# 3.net
KiCad netlist of a schematic drawn in Altium Designer
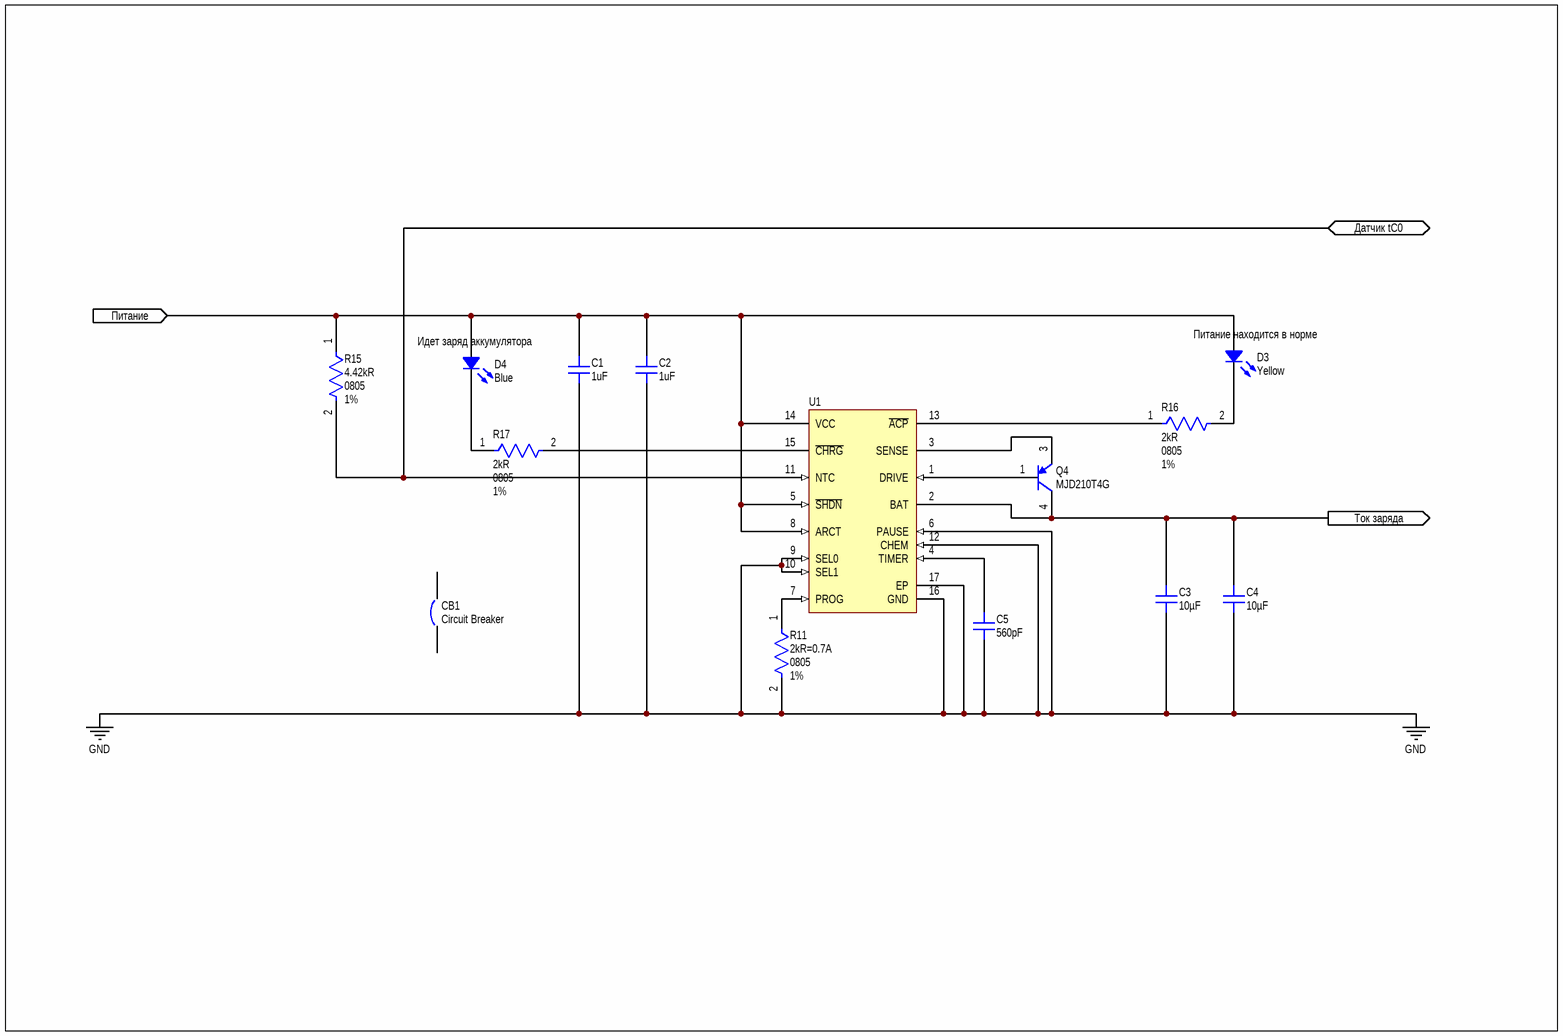
[diagram p0: Блок3.SchDoc]

(export (version "E")
  (design (tool "Eeschema 10.0.6"))
  (components
    (comp (ref "C1")
      (value "1uF")
      (footprint "CAP 1206_3216 - 1.2MM")
      (description "CAP CER 1UF 50V X7R 1206")
      (fields (field (name "PART NUMBER") "C1206C105M5RACTU") (field (name "MANUFACTURER") "KEMET"))
      (libsource (lib "Celestial Altium Library - altium_library") (part "Capacitor"))
    )
    (comp (ref "C2")
      (value "1uF")
      (footprint "CAP 1206_3216 - 1.2MM")
      (description "CAP CER 1UF 50V X7R 1206")
      (fields (field (name "PART NUMBER") "C1206C105M5RACTU") (field (name "MANUFACTURER") "KEMET"))
      (libsource (lib "Celestial Altium Library - altium_library") (part "Capacitor"))
    )
    (comp (ref "C3")
      (value "10µF")
      (footprint "CAP 1206_3216 - 1.0MM")
      (description "CAP CER 10UF 16V X5R 1206")
      (fields (field (name "PART NUMBER") "EMK316BJ106MD-T") (field (name "MANUFACTURER") "Taiyo Yuden"))
      (libsource (lib "Celestial Altium Library - altium_library") (part "Capacitor"))
    )
    (comp (ref "C4")
      (value "10µF")
      (footprint "CAP 1206_3216 - 1.0MM")
      (description "CAP CER 10UF 16V X5R 1206")
      (fields (field (name "PART NUMBER") "EMK316BJ106MD-T") (field (name "MANUFACTURER") "Taiyo Yuden"))
      (libsource (lib "Celestial Altium Library - altium_library") (part "Capacitor"))
    )
    (comp (ref "C5")
      (value "560pF")
      (footprint "CAP 1206_3216 - 0.8MM")
      (description "CAP CER 560PF 50V NPO 1206")
      (fields (field (name "PART NUMBER") "CC1206JRNPO9BN561") (field (name "MANUFACTURER") "Yageo"))
      (libsource (lib "Celestial Altium Library - altium_library") (part "Capacitor"))
    )
    (comp (ref "CB1")
      (value "Circuit Breaker")
      (footprint "SPST-2")
      (fields (field (name "PUBLISHER") "Altium Limited"))
      (libsource (lib "Miscellaneous Devices") (part "Circuit Breaker"))
    )
    (comp (ref "D3")
      (value "Yellow")
      (footprint "LED 1206_3216 YELLOW")
      (description "LED YELLOW CLEAR 2SMD")
      (fields
        (field (name "PART NUMBER") "APTD3216SYCK")
        (field (name "MANUFACTURER") "Kingbright")
        (field (name "PARAMETER 1") "Питание находится в норме")
      )
      (libsource (lib "Celestial Altium Library - altium_library") (part "LED"))
    )
    (comp (ref "D4")
      (value "Blue")
      (footprint "LED 1206_3216 BLUE")
      (description "LED BLUE CLEAR 1206 SMD")
      (fields
        (field (name "PART NUMBER") "IN-S126ATB")
        (field (name "MANUFACTURER") "Inolux")
        (field (name "PARAMETER 1") "Идет заряд аккумулятора")
      )
      (libsource (lib "Celestial Altium Library - altium_library") (part "LED"))
    )
    (comp (ref "Q4")
      (value "MJD210T4G")
      (footprint "ONSC-DPAK-3-369C-01_V")
      (description "Complementary Plastic Power Transistor, PNP Silicon, 3-Pin DPAK, Pb-Free, Tape and Reel")
      (fields (field (name "MANUFACTURER") "On Semiconductor"))
      (libsource (lib "Altium Content Vault") (part "ONSC-PNP-B1E3C4-3_A"))
    )
    (comp (ref "R11")
      (value "MC01W0805110K")
      (footprint "FP-MC01W0805-IPC_C")
      (description "Resistor, 10K, 0.1W, 1%, 0805, Reel")
      (fields
        (field (name "RESISTANCE") "2kR=0.7A")
        (field (name "CASE/PACKAGE") "0805")
        (field (name "TOLERANCE") "1%")
        (field (name "MANUFACTURER") "Multicomp")
      )
      (libsource (lib "Altium Content Vault") (part "1029c3af85768c4190bb7ad29bc67b5"))
    )
    (comp (ref "R15")
      (value "MC01W0805110K")
      (footprint "FP-MC01W0805-IPC_C")
      (description "Resistor, 10K, 0.1W, 1%, 0805, Reel")
      (fields
        (field (name "RESISTANCE") "4.42kR")
        (field (name "CASE/PACKAGE") "0805")
        (field (name "TOLERANCE") "1%")
        (field (name "MANUFACTURER") "Multicomp")
      )
      (libsource (lib "Altium Content Vault") (part "1029c3af85768c4190bb7ad29bc67b5"))
    )
    (comp (ref "R16")
      (value "MC01W0805110K")
      (footprint "FP-MC01W0805-IPC_C")
      (description "Resistor, 10K, 0.1W, 1%, 0805, Reel")
      (fields
        (field (name "RESISTANCE") "2kR")
        (field (name "CASE/PACKAGE") "0805")
        (field (name "TOLERANCE") "1%")
        (field (name "MANUFACTURER") "Multicomp")
      )
      (libsource (lib "Altium Content Vault") (part "1029c3af85768c4190bb7ad29bc67b5"))
    )
    (comp (ref "R17")
      (value "MC01W0805110K")
      (footprint "FP-MC01W0805-IPC_C")
      (description "Resistor, 10K, 0.1W, 1%, 0805, Reel")
      (fields
        (field (name "RESISTANCE") "2kR")
        (field (name "CASE/PACKAGE") "0805")
        (field (name "TOLERANCE") "1%")
        (field (name "MANUFACTURER") "Multicomp")
      )
      (libsource (lib "Altium Content Vault") (part "1029c3af85768c4190bb7ad29bc67b5"))
    )
    (comp (ref "U1")
      (value "LTC4060EDHC#PBF")
      (footprint "LT-DHC-16_V")
      (fields (field (name "MANUFACTURER") "Linear Technology"))
      (libsource (lib "Altium Content Vault") (part "LT-LTC4060-DHC-16"))
    )
  )
  (nets
    (net (code "1") (name "/Датчик tC0") (class "Default")
      (node (ref "R15") (pin "2") (pinfunction "2_2") (pintype "passive"))
      (node (ref "U1") (pin "11") (pinfunction "NTC_11") (pintype "input"))
    )
    (net (code "2") (name "/Питание") (class "Default")
      (node (ref "C1") (pin "2") (pinfunction "2_2") (pintype "passive"))
      (node (ref "C2") (pin "2") (pinfunction "2_2") (pintype "passive"))
      (node (ref "D3") (pin "1") (pinfunction "1_1") (pintype "passive"))
      (node (ref "D4") (pin "1") (pinfunction "1_1") (pintype "passive"))
      (node (ref "R15") (pin "1") (pinfunction "1_1") (pintype "passive"))
      (node (ref "U1") (pin "14") (pinfunction "VCC_14") (pintype "power_in"))
      (node (ref "U1") (pin "5") (pinfunction "~{SHDN}_5") (pintype "input"))
      (node (ref "U1") (pin "8") (pinfunction "ARCT_8") (pintype "input"))
    )
    (net (code "3") (name "/Ток заряда") (class "Default")
      (node (ref "C3") (pin "2") (pinfunction "2_2") (pintype "passive"))
      (node (ref "C4") (pin "2") (pinfunction "2_2") (pintype "passive"))
      (node (ref "Q4") (pin "4") (pinfunction "C_4") (pintype "passive"))
      (node (ref "U1") (pin "2") (pinfunction "BAT_2") (pintype "passive"))
    )
    (net (code "4") (name "GND") (class "Default")
      (node (ref "C1") (pin "1") (pinfunction "1_1") (pintype "passive"))
      (node (ref "C2") (pin "1") (pinfunction "1_1") (pintype "passive"))
      (node (ref "C3") (pin "1") (pinfunction "1_1") (pintype "passive"))
      (node (ref "C4") (pin "1") (pinfunction "1_1") (pintype "passive"))
      (node (ref "C5") (pin "1") (pinfunction "1_1") (pintype "passive"))
      (node (ref "R11") (pin "2") (pinfunction "2_2") (pintype "passive"))
      (node (ref "U1") (pin "10") (pinfunction "SEL1_10") (pintype "input"))
      (node (ref "U1") (pin "12") (pinfunction "CHEM_12") (pintype "input"))
      (node (ref "U1") (pin "16") (pinfunction "GND_16") (pintype "power_in"))
      (node (ref "U1") (pin "17") (pinfunction "EP_17") (pintype "power_in"))
      (node (ref "U1") (pin "6") (pinfunction "PAUSE_6") (pintype "input"))
      (node (ref "U1") (pin "9") (pinfunction "SEL0_9") (pintype "input"))
    )
    (net (code "5") (name "Net-(D3-Pad2)") (class "Default")
      (node (ref "D3") (pin "2") (pinfunction "2_2") (pintype "passive"))
      (node (ref "R16") (pin "2") (pinfunction "2_2") (pintype "passive"))
    )
    (net (code "6") (name "Net-(D4-Pad2)") (class "Default")
      (node (ref "D4") (pin "2") (pinfunction "2_2") (pintype "passive"))
      (node (ref "R17") (pin "1") (pinfunction "1_1") (pintype "passive"))
    )
    (net (code "7") (name "Net-(Q4-B)") (class "Default")
      (node (ref "Q4") (pin "1") (pinfunction "B_1") (pintype "passive"))
      (node (ref "U1") (pin "1") (pinfunction "DRIVE_1") (pintype "input"))
    )
    (net (code "8") (name "Net-(Q4-E)") (class "Default")
      (node (ref "Q4") (pin "3") (pinfunction "E_3") (pintype "passive"))
      (node (ref "U1") (pin "3") (pinfunction "SENSE_3") (pintype "passive"))
    )
    (net (code "9") (name "Net-(U1-PROG)") (class "Default")
      (node (ref "R11") (pin "1") (pinfunction "1_1") (pintype "passive"))
      (node (ref "U1") (pin "7") (pinfunction "PROG_7") (pintype "input"))
    )
    (net (code "10") (name "Net-(U1-TIMER)") (class "Default")
      (node (ref "C5") (pin "2") (pinfunction "2_2") (pintype "passive"))
      (node (ref "U1") (pin "4") (pinfunction "TIMER_4") (pintype "input"))
    )
    (net (code "11") (name "Net-(U1-~{ACP})") (class "Default")
      (node (ref "R16") (pin "1") (pinfunction "1_1") (pintype "passive"))
      (node (ref "U1") (pin "13") (pinfunction "~{ACP}_13") (pintype "tri_state"))
    )
    (net (code "12") (name "Net-(U1-~{CHRG})") (class "Default")
      (node (ref "R17") (pin "2") (pinfunction "2_2") (pintype "passive"))
      (node (ref "U1") (pin "15") (pinfunction "~{CHRG}_15") (pintype "tri_state"))
    )
    (net (code "13") (name "unconnected-(CB1-Pad1)") (class "Default")
      (node (ref "CB1") (pin "1") (pinfunction "1_1") (pintype "passive"))
    )
    (net (code "14") (name "unconnected-(CB1-Pad2)") (class "Default")
      (node (ref "CB1") (pin "2") (pinfunction "2_2") (pintype "passive"))
    )
  )
)
